# RS-485-USB.net
KiCad netlist of a schematic drawn in Altium Designer
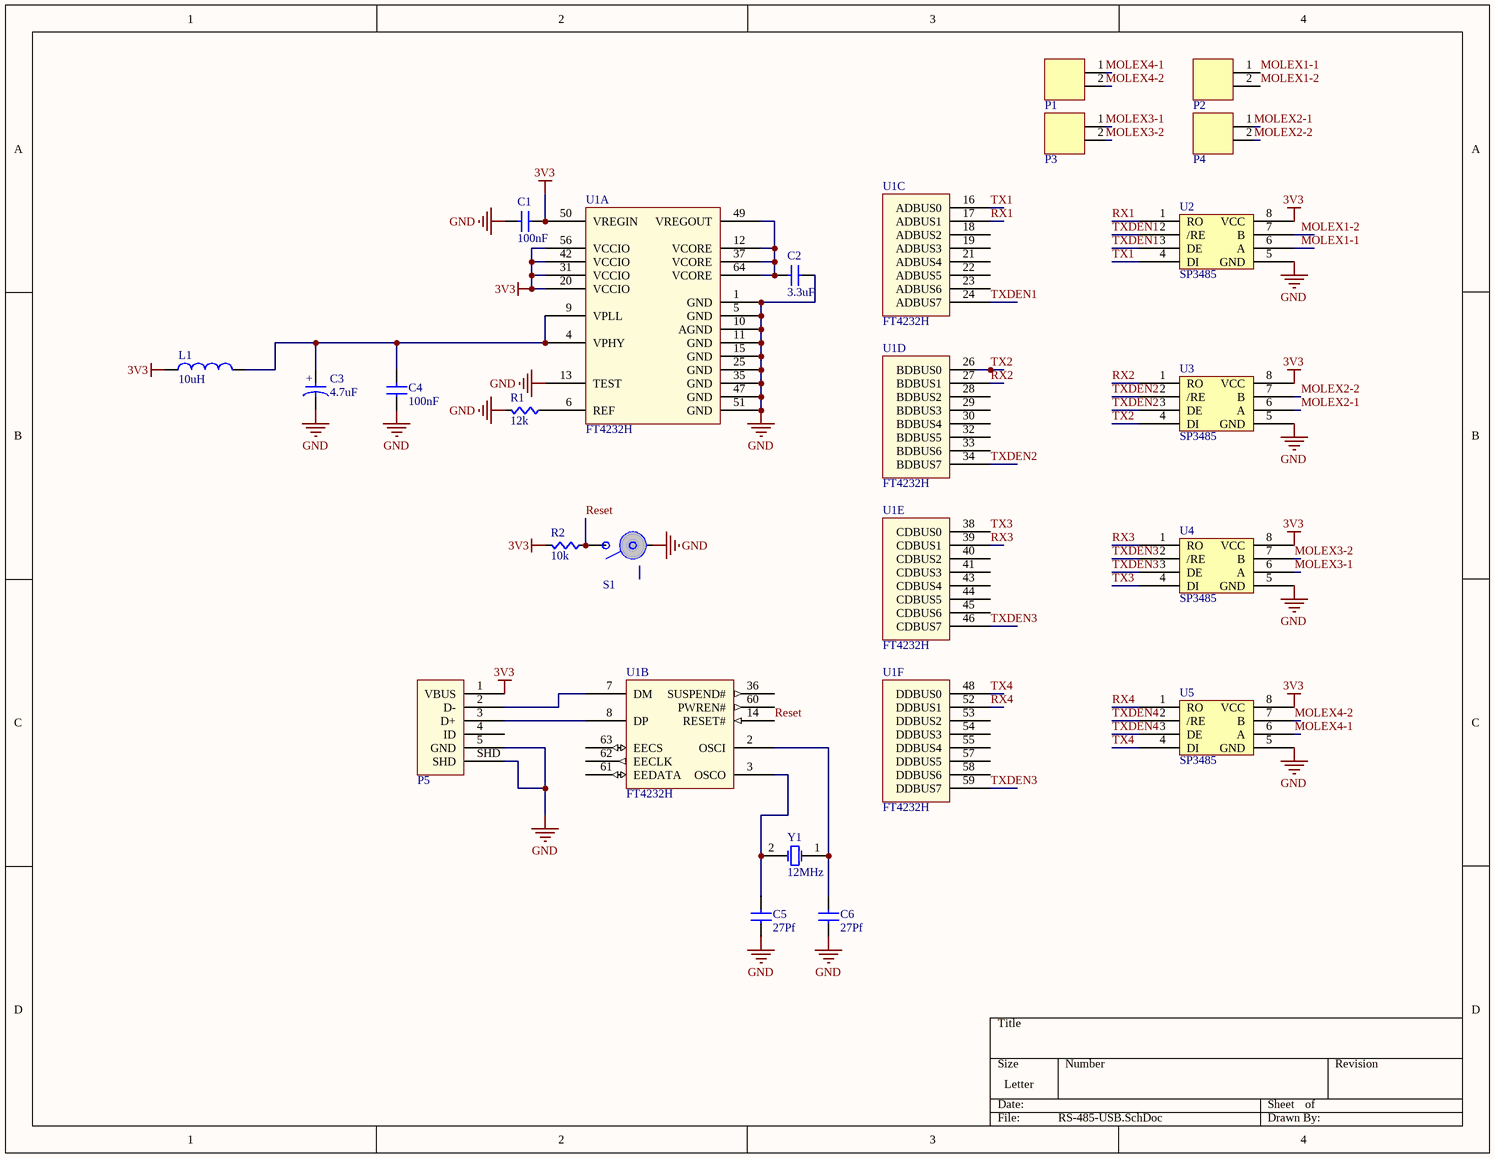
[diagram p0: RS-485-USB.SchDoc]

(export (version "E")
  (design (tool "Eeschema 10.0.6"))
  (components
    (comp (ref "C1")
      (value "100nF")
      (footprint "CAPC0603")
      (fields (field (name "Comment") "Cap"))
      (libsource (lib "SubjuGator8") (part "Cap"))
    )
    (comp (ref "C2")
      (value "3.3uF")
      (footprint "CAPC0603")
      (fields (field (name "Comment") "Cap"))
      (libsource (lib "SubjuGator8") (part "Cap"))
    )
    (comp (ref "C3")
      (value "4.7uF")
      (footprint "CAPP0603")
      (fields (field (name "Comment") "CapPol"))
      (libsource (lib "SubjuGator8") (part "CapPol"))
    )
    (comp (ref "C4")
      (value "100nF")
      (footprint "CAPC0603")
      (fields (field (name "Comment") "Cap"))
      (libsource (lib "SubjuGator8") (part "Cap"))
    )
    (comp (ref "C5")
      (value "27Pf")
      (footprint "CAPC0603")
      (fields (field (name "Comment") "Cap"))
      (libsource (lib "SubjuGator8") (part "Cap"))
    )
    (comp (ref "C6")
      (value "27Pf")
      (footprint "CAPC0603")
      (fields (field (name "Comment") "Cap"))
      (libsource (lib "SubjuGator8") (part "Cap"))
    )
    (comp (ref "L1")
      (value "Inductor")
      (footprint "CDPH4D19F")
      (fields (field (name "INDUCTANCE") "10uH"))
      (libsource (lib "SubjuGator8") (part "Inductor"))
    )
    (comp (ref "P1")
      (value "2-pin Horz Sherlock")
      (footprint "MOLEX-HDR-1X2-SHERLOCK-HORZ")
      (fields
        (field (name "MANUFACTURER PART NUMBER") "0353630260")
        (field (name "MANUFACTURER") "Molex Inc")
      )
      (libsource (lib "SubjuGator8") (part "MOLEX-HDR-1x2-SHERLOCK_RA"))
    )
    (comp (ref "P2")
      (value "2-pin Horz Sherlock")
      (footprint "MOLEX-HDR-1X2-SHERLOCK-HORZ")
      (fields
        (field (name "MANUFACTURER PART NUMBER") "0353630260")
        (field (name "MANUFACTURER") "Molex Inc")
      )
      (libsource (lib "SubjuGator8") (part "MOLEX-HDR-1x2-SHERLOCK_RA"))
    )
    (comp (ref "P3")
      (value "2-pin Horz Sherlock")
      (footprint "MOLEX-HDR-1X2-SHERLOCK-HORZ")
      (fields
        (field (name "MANUFACTURER PART NUMBER") "0353630260")
        (field (name "MANUFACTURER") "Molex Inc")
      )
      (libsource (lib "SubjuGator8") (part "MOLEX-HDR-1x2-SHERLOCK_RA"))
    )
    (comp (ref "P4")
      (value "2-pin Horz Sherlock")
      (footprint "MOLEX-HDR-1X2-SHERLOCK-HORZ")
      (fields
        (field (name "MANUFACTURER PART NUMBER") "0353630260")
        (field (name "MANUFACTURER") "Molex Inc")
      )
      (libsource (lib "SubjuGator8") (part "MOLEX-HDR-1x2-SHERLOCK_RA"))
    )
    (comp (ref "P5")
      (value "USB Micro")
      (footprint "10118192-0001LF")
      (description "USB Mini B Metal Shield SMT")
      (libsource (lib "SubjuGator8") (part "USB Micro"))
    )
    (comp (ref "R1")
      (value "12k")
      (footprint "RES0603")
      (fields (field (name "Comment") "Res"))
      (libsource (lib "SubjuGator8") (part "Res"))
    )
    (comp (ref "R2")
      (value "10k")
      (footprint "RES0603")
      (fields (field (name "Comment") "Res"))
      (libsource (lib "SubjuGator8") (part "Res"))
    )
    (comp (ref "S1")
      (value "Button")
      (footprint "PTS645xxxxSMTR92")
      (description "SPST Button")
      (libsource (lib "SubjuGator8") (part "Button"))
    )
    (comp (ref "U1")
      (value "FT4232H")
      (footprint "FT4232HL")
      (description "Quad High Speed USB to Multipurpose UART/MPSSE")
      (libsource (lib "SubjuGator8") (part "FT4232H"))
    )
    (comp (ref "U2")
      (value "SP3485")
      (footprint "SP3485")
      (description "IC TXRX RS485 HALF DUPLEX 8NSOIC")
      (libsource (lib "SubjuGator8") (part "SP3485"))
    )
    (comp (ref "U3")
      (value "SP3485")
      (footprint "SP3485")
      (description "IC TXRX RS485 HALF DUPLEX 8NSOIC")
      (libsource (lib "SubjuGator8") (part "SP3485"))
    )
    (comp (ref "U4")
      (value "SP3485")
      (footprint "SP3485")
      (description "IC TXRX RS485 HALF DUPLEX 8NSOIC")
      (libsource (lib "SubjuGator8") (part "SP3485"))
    )
    (comp (ref "U5")
      (value "SP3485")
      (footprint "SP3485")
      (description "IC TXRX RS485 HALF DUPLEX 8NSOIC")
      (libsource (lib "SubjuGator8") (part "SP3485"))
    )
    (comp (ref "Y1")
      (value "12MHz")
      (footprint "R38")
      (description "Crystal Oscillator")
      (fields (field (name "PUBLISHER") "Altium Limited"))
      (libsource (lib "Miscellaneous Devices") (part "XTAL"))
    )
  )
  (nets
    (net (code "1") (name "/MOLEX1-1") (class "Default")
      (node (ref "P2") (pin "1") (pinfunction "1_1") (pintype "passive"))
      (node (ref "U2") (pin "6") (pinfunction "A_6") (pintype "passive"))
    )
    (net (code "2") (name "/MOLEX1-2") (class "Default")
      (node (ref "P2") (pin "2") (pinfunction "2_2") (pintype "passive"))
      (node (ref "U2") (pin "7") (pinfunction "B_7") (pintype "passive"))
    )
    (net (code "3") (name "/MOLEX2-1") (class "Default")
      (node (ref "P4") (pin "1") (pinfunction "1_1") (pintype "passive"))
      (node (ref "U3") (pin "6") (pinfunction "A_6") (pintype "passive"))
    )
    (net (code "4") (name "/MOLEX2-2") (class "Default")
      (node (ref "P4") (pin "2") (pinfunction "2_2") (pintype "passive"))
      (node (ref "U3") (pin "7") (pinfunction "B_7") (pintype "passive"))
    )
    (net (code "5") (name "/MOLEX3-1") (class "Default")
      (node (ref "P3") (pin "1") (pinfunction "1_1") (pintype "passive"))
      (node (ref "U4") (pin "6") (pinfunction "A_6") (pintype "passive"))
    )
    (net (code "6") (name "/MOLEX3-2") (class "Default")
      (node (ref "P3") (pin "2") (pinfunction "2_2") (pintype "passive"))
      (node (ref "U4") (pin "7") (pinfunction "B_7") (pintype "passive"))
    )
    (net (code "7") (name "/MOLEX4-1") (class "Default")
      (node (ref "P1") (pin "1") (pinfunction "1_1") (pintype "passive"))
      (node (ref "U5") (pin "6") (pinfunction "A_6") (pintype "passive"))
    )
    (net (code "8") (name "/MOLEX4-2") (class "Default")
      (node (ref "P1") (pin "2") (pinfunction "2_2") (pintype "passive"))
      (node (ref "U5") (pin "7") (pinfunction "B_7") (pintype "passive"))
    )
    (net (code "9") (name "/RX1") (class "Default")
      (node (ref "U1") (pin "17") (pinfunction "ADBUS1_17") (pintype "passive"))
      (node (ref "U2") (pin "1") (pinfunction "RO_1") (pintype "passive"))
    )
    (net (code "10") (name "/RX2") (class "Default")
      (node (ref "U1") (pin "27") (pinfunction "BDBUS1_27") (pintype "passive"))
      (node (ref "U3") (pin "1") (pinfunction "RO_1") (pintype "passive"))
    )
    (net (code "11") (name "/RX3") (class "Default")
      (node (ref "U1") (pin "39") (pinfunction "CDBUS1_39") (pintype "passive"))
      (node (ref "U4") (pin "1") (pinfunction "RO_1") (pintype "passive"))
    )
    (net (code "12") (name "/RX4") (class "Default")
      (node (ref "U1") (pin "52") (pinfunction "DDBUS1_52") (pintype "passive"))
      (node (ref "U5") (pin "1") (pinfunction "RO_1") (pintype "passive"))
    )
    (net (code "13") (name "/Reset") (class "Default")
      (node (ref "R2") (pin "2") (pinfunction "B_2") (pintype "passive"))
      (node (ref "S1") (pin "B") (pinfunction "B_B") (pintype "passive"))
      (node (ref "U1") (pin "14") (pinfunction "RESET#_14") (pintype "input"))
    )
    (net (code "14") (name "/TX1") (class "Default")
      (node (ref "U1") (pin "16") (pinfunction "ADBUS0_16") (pintype "passive"))
      (node (ref "U2") (pin "4") (pinfunction "DI_4") (pintype "passive"))
    )
    (net (code "15") (name "/TX2") (class "Default")
      (node (ref "U1") (pin "26") (pinfunction "BDBUS0_26") (pintype "passive"))
      (node (ref "U3") (pin "4") (pinfunction "DI_4") (pintype "passive"))
    )
    (net (code "16") (name "/TX3") (class "Default")
      (node (ref "U1") (pin "38") (pinfunction "CDBUS0_38") (pintype "passive"))
      (node (ref "U4") (pin "4") (pinfunction "DI_4") (pintype "passive"))
    )
    (net (code "17") (name "/TX4") (class "Default")
      (node (ref "U1") (pin "48") (pinfunction "DDBUS0_48") (pintype "passive"))
      (node (ref "U5") (pin "4") (pinfunction "DI_4") (pintype "passive"))
    )
    (net (code "18") (name "/TXDEN1") (class "Default")
      (node (ref "U1") (pin "24") (pinfunction "ADBUS7_24") (pintype "passive"))
      (node (ref "U2") (pin "2") (pinfunction "/RE_2") (pintype "passive"))
      (node (ref "U2") (pin "3") (pinfunction "DE_3") (pintype "passive"))
    )
    (net (code "19") (name "/TXDEN2") (class "Default")
      (node (ref "U1") (pin "34") (pinfunction "BDBUS7_34") (pintype "passive"))
      (node (ref "U3") (pin "2") (pinfunction "/RE_2") (pintype "passive"))
      (node (ref "U3") (pin "3") (pinfunction "DE_3") (pintype "passive"))
    )
    (net (code "20") (name "/TXDEN3") (class "Default")
      (node (ref "U1") (pin "46") (pinfunction "CDBUS7_46") (pintype "passive"))
      (node (ref "U1") (pin "59") (pinfunction "DDBUS7_59") (pintype "passive"))
      (node (ref "U4") (pin "2") (pinfunction "/RE_2") (pintype "passive"))
      (node (ref "U4") (pin "3") (pinfunction "DE_3") (pintype "passive"))
    )
    (net (code "21") (name "/TXDEN4") (class "Default")
      (node (ref "U5") (pin "2") (pinfunction "/RE_2") (pintype "passive"))
      (node (ref "U5") (pin "3") (pinfunction "DE_3") (pintype "passive"))
    )
    (net (code "22") (name "3V3") (class "Default")
      (node (ref "C1") (pin "2") (pinfunction "B_2") (pintype "passive"))
      (node (ref "L1") (pin "1") (pinfunction "A_1") (pintype "passive"))
      (node (ref "P5") (pin "1") (pinfunction "VBUS_1") (pintype "passive"))
      (node (ref "R2") (pin "1") (pinfunction "A_1") (pintype "passive"))
      (node (ref "U1") (pin "20") (pinfunction "VCCIO_20") (pintype "power_in"))
      (node (ref "U1") (pin "31") (pinfunction "VCCIO_31") (pintype "power_in"))
      (node (ref "U1") (pin "42") (pinfunction "VCCIO_42") (pintype "power_in"))
      (node (ref "U1") (pin "50") (pinfunction "VREGIN_50") (pintype "power_in"))
      (node (ref "U1") (pin "56") (pinfunction "VCCIO_56") (pintype "power_in"))
      (node (ref "U2") (pin "8") (pinfunction "VCC_8") (pintype "passive"))
      (node (ref "U3") (pin "8") (pinfunction "VCC_8") (pintype "passive"))
      (node (ref "U4") (pin "8") (pinfunction "VCC_8") (pintype "passive"))
      (node (ref "U5") (pin "8") (pinfunction "VCC_8") (pintype "passive"))
    )
    (net (code "23") (name "GND") (class "Default")
      (node (ref "C1") (pin "1") (pinfunction "A_1") (pintype "passive"))
      (node (ref "C2") (pin "1") (pinfunction "A_1") (pintype "passive"))
      (node (ref "C3") (pin "2") (pinfunction "B_2") (pintype "passive"))
      (node (ref "C4") (pin "1") (pinfunction "A_1") (pintype "passive"))
      (node (ref "C5") (pin "2") (pinfunction "B_2") (pintype "passive"))
      (node (ref "C6") (pin "2") (pinfunction "B_2") (pintype "passive"))
      (node (ref "P5") (pin "5") (pinfunction "GND_5") (pintype "passive"))
      (node (ref "P5") (pin "SHD") (pinfunction "SHD_SHD") (pintype "passive"))
      (node (ref "R1") (pin "1") (pinfunction "A_1") (pintype "passive"))
      (node (ref "S1") (pin "A") (pinfunction "A_A") (pintype "passive"))
      (node (ref "U1") (pin "1") (pinfunction "GND_1") (pintype "power_in"))
      (node (ref "U1") (pin "10") (pinfunction "AGND_10") (pintype "power_in"))
      (node (ref "U1") (pin "11") (pinfunction "GND_11") (pintype "power_in"))
      (node (ref "U1") (pin "13") (pinfunction "TEST_13") (pintype "passive"))
      (node (ref "U1") (pin "15") (pinfunction "GND_15") (pintype "power_in"))
      (node (ref "U1") (pin "25") (pinfunction "GND_25") (pintype "power_in"))
      (node (ref "U1") (pin "35") (pinfunction "GND_35") (pintype "power_in"))
      (node (ref "U1") (pin "47") (pinfunction "GND_47") (pintype "power_in"))
      (node (ref "U1") (pin "5") (pinfunction "GND_5") (pintype "power_in"))
      (node (ref "U1") (pin "51") (pinfunction "GND_51") (pintype "power_in"))
      (node (ref "U2") (pin "5") (pinfunction "GND_5") (pintype "passive"))
      (node (ref "U3") (pin "5") (pinfunction "GND_5") (pintype "passive"))
      (node (ref "U4") (pin "5") (pinfunction "GND_5") (pintype "passive"))
      (node (ref "U5") (pin "5") (pinfunction "GND_5") (pintype "passive"))
    )
    (net (code "24") (name "Net-(C2-B)") (class "Default")
      (node (ref "C2") (pin "2") (pinfunction "B_2") (pintype "passive"))
      (node (ref "U1") (pin "12") (pinfunction "VCORE_12") (pintype "power_in"))
      (node (ref "U1") (pin "37") (pinfunction "VCORE_37") (pintype "power_in"))
      (node (ref "U1") (pin "49") (pinfunction "VREGOUT_49") (pintype "power_in"))
      (node (ref "U1") (pin "64") (pinfunction "VCORE_64") (pintype "power_in"))
    )
    (net (code "25") (name "Net-(C3-A)") (class "Default")
      (node (ref "C3") (pin "1") (pinfunction "A_1") (pintype "passive"))
      (node (ref "C4") (pin "2") (pinfunction "B_2") (pintype "passive"))
      (node (ref "L1") (pin "2") (pinfunction "B_2") (pintype "passive"))
      (node (ref "U1") (pin "4") (pinfunction "VPHY_4") (pintype "power_in"))
      (node (ref "U1") (pin "9") (pinfunction "VPLL_9") (pintype "power_in"))
    )
    (net (code "26") (name "Net-(C5-A)") (class "Default")
      (node (ref "C5") (pin "1") (pinfunction "A_1") (pintype "passive"))
      (node (ref "U1") (pin "3") (pinfunction "OSCO_3") (pintype "passive"))
      (node (ref "Y1") (pin "2") (pinfunction "OSC2_2") (pintype "passive"))
    )
    (net (code "27") (name "Net-(C6-A)") (class "Default")
      (node (ref "C6") (pin "1") (pinfunction "A_1") (pintype "passive"))
      (node (ref "U1") (pin "2") (pinfunction "OSCI_2") (pintype "passive"))
      (node (ref "Y1") (pin "1") (pinfunction "OSC1_1") (pintype "passive"))
    )
    (net (code "28") (name "Net-(P5-D+)") (class "Default")
      (node (ref "P5") (pin "3") (pinfunction "D+_3") (pintype "passive"))
      (node (ref "U1") (pin "8") (pinfunction "DP_8") (pintype "passive"))
    )
    (net (code "29") (name "Net-(P5-D-)") (class "Default")
      (node (ref "P5") (pin "2") (pinfunction "D-_2") (pintype "passive"))
      (node (ref "U1") (pin "7") (pinfunction "DM_7") (pintype "passive"))
    )
    (net (code "30") (name "Net-(R1-B)") (class "Default")
      (node (ref "R1") (pin "2") (pinfunction "B_2") (pintype "passive"))
      (node (ref "U1") (pin "6") (pinfunction "REF_6") (pintype "passive"))
    )
    (net (code "31") (name "unconnected-(P5-ID-Pad4)") (class "Default")
      (node (ref "P5") (pin "4") (pinfunction "ID_4") (pintype "passive"))
    )
    (net (code "32") (name "unconnected-(U1B-EECLK-Pad62)") (class "Default")
      (node (ref "U1") (pin "62") (pinfunction "EECLK_62") (pintype "output"))
    )
    (net (code "33") (name "unconnected-(U1B-EECS-Pad63)") (class "Default")
      (node (ref "U1") (pin "63") (pinfunction "EECS_63") (pintype "bidirectional"))
    )
    (net (code "34") (name "unconnected-(U1B-EEDATA-Pad61)") (class "Default")
      (node (ref "U1") (pin "61") (pinfunction "EEDATA_61") (pintype "bidirectional"))
    )
    (net (code "35") (name "unconnected-(U1B-PWREN#-Pad60)") (class "Default")
      (node (ref "U1") (pin "60") (pinfunction "PWREN#_60") (pintype "output"))
    )
    (net (code "36") (name "unconnected-(U1B-SUSPEND#-Pad36)") (class "Default")
      (node (ref "U1") (pin "36") (pinfunction "SUSPEND#_36") (pintype "output"))
    )
    (net (code "37") (name "unconnected-(U1C-ADBUS2-Pad18)") (class "Default")
      (node (ref "U1") (pin "18") (pinfunction "ADBUS2_18") (pintype "passive"))
    )
    (net (code "38") (name "unconnected-(U1C-ADBUS3-Pad19)") (class "Default")
      (node (ref "U1") (pin "19") (pinfunction "ADBUS3_19") (pintype "passive"))
    )
    (net (code "39") (name "unconnected-(U1C-ADBUS4-Pad21)") (class "Default")
      (node (ref "U1") (pin "21") (pinfunction "ADBUS4_21") (pintype "passive"))
    )
    (net (code "40") (name "unconnected-(U1C-ADBUS5-Pad22)") (class "Default")
      (node (ref "U1") (pin "22") (pinfunction "ADBUS5_22") (pintype "passive"))
    )
    (net (code "41") (name "unconnected-(U1C-ADBUS6-Pad23)") (class "Default")
      (node (ref "U1") (pin "23") (pinfunction "ADBUS6_23") (pintype "passive"))
    )
    (net (code "42") (name "unconnected-(U1D-BDBUS2-Pad28)") (class "Default")
      (node (ref "U1") (pin "28") (pinfunction "BDBUS2_28") (pintype "passive"))
    )
    (net (code "43") (name "unconnected-(U1D-BDBUS3-Pad29)") (class "Default")
      (node (ref "U1") (pin "29") (pinfunction "BDBUS3_29") (pintype "passive"))
    )
    (net (code "44") (name "unconnected-(U1D-BDBUS4-Pad30)") (class "Default")
      (node (ref "U1") (pin "30") (pinfunction "BDBUS4_30") (pintype "passive"))
    )
    (net (code "45") (name "unconnected-(U1D-BDBUS5-Pad32)") (class "Default")
      (node (ref "U1") (pin "32") (pinfunction "BDBUS5_32") (pintype "passive"))
    )
    (net (code "46") (name "unconnected-(U1D-BDBUS6-Pad33)") (class "Default")
      (node (ref "U1") (pin "33") (pinfunction "BDBUS6_33") (pintype "passive"))
    )
    (net (code "47") (name "unconnected-(U1E-CDBUS2-Pad40)") (class "Default")
      (node (ref "U1") (pin "40") (pinfunction "CDBUS2_40") (pintype "passive"))
    )
    (net (code "48") (name "unconnected-(U1E-CDBUS3-Pad41)") (class "Default")
      (node (ref "U1") (pin "41") (pinfunction "CDBUS3_41") (pintype "passive"))
    )
    (net (code "49") (name "unconnected-(U1E-CDBUS4-Pad43)") (class "Default")
      (node (ref "U1") (pin "43") (pinfunction "CDBUS4_43") (pintype "passive"))
    )
    (net (code "50") (name "unconnected-(U1E-CDBUS5-Pad44)") (class "Default")
      (node (ref "U1") (pin "44") (pinfunction "CDBUS5_44") (pintype "passive"))
    )
    (net (code "51") (name "unconnected-(U1E-CDBUS6-Pad45)") (class "Default")
      (node (ref "U1") (pin "45") (pinfunction "CDBUS6_45") (pintype "passive"))
    )
    (net (code "52") (name "unconnected-(U1F-DDBUS2-Pad53)") (class "Default")
      (node (ref "U1") (pin "53") (pinfunction "DDBUS2_53") (pintype "passive"))
    )
    (net (code "53") (name "unconnected-(U1F-DDBUS3-Pad54)") (class "Default")
      (node (ref "U1") (pin "54") (pinfunction "DDBUS3_54") (pintype "passive"))
    )
    (net (code "54") (name "unconnected-(U1F-DDBUS4-Pad55)") (class "Default")
      (node (ref "U1") (pin "55") (pinfunction "DDBUS4_55") (pintype "passive"))
    )
    (net (code "55") (name "unconnected-(U1F-DDBUS5-Pad57)") (class "Default")
      (node (ref "U1") (pin "57") (pinfunction "DDBUS5_57") (pintype "passive"))
    )
    (net (code "56") (name "unconnected-(U1F-DDBUS6-Pad58)") (class "Default")
      (node (ref "U1") (pin "58") (pinfunction "DDBUS6_58") (pintype "passive"))
    )
  )
)
